# ThermistorFlex.net
KiCad netlist of a schematic drawn in EasyEDA Pro
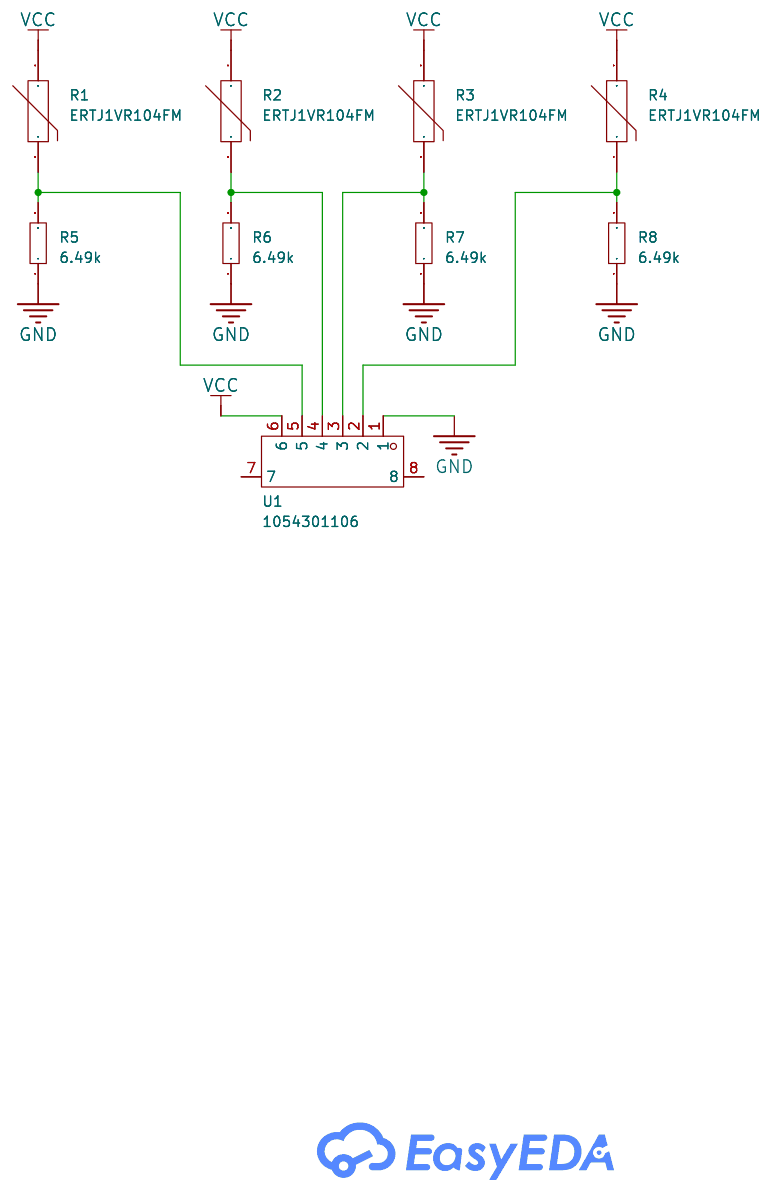
[diagram p0: schematic sheet]

(export (version "E")
  (design (tool "Eeschema 10.0.6"))
  (components
    (comp (ref "R1")
      (value "ERTJ1VR104FM")
      (footprint "easyedapro:R0603")
      (fields (field (name "Manufacturer") "PANASONIC(松下)"))
      (libsource (lib "easyedapro") (part "ERTJ1VR104FM"))
    )
    (comp (ref "R2")
      (value "ERTJ1VR104FM")
      (footprint "easyedapro:R0603")
      (fields (field (name "Manufacturer") "PANASONIC(松下)"))
      (libsource (lib "easyedapro") (part "ERTJ1VR104FM"))
    )
    (comp (ref "R3")
      (value "ERTJ1VR104FM")
      (footprint "easyedapro:R0603")
      (fields (field (name "Manufacturer") "PANASONIC(松下)"))
      (libsource (lib "easyedapro") (part "ERTJ1VR104FM"))
    )
    (comp (ref "R4")
      (value "ERTJ1VR104FM")
      (footprint "easyedapro:R0603")
      (fields (field (name "Manufacturer") "PANASONIC(松下)"))
      (libsource (lib "easyedapro") (part "ERTJ1VR104FM"))
    )
    (comp (ref "R5")
      (value "6.49k")
      (footprint "easyedapro:R0603")
      (libsource (lib "easyedapro") (part "Res"))
    )
    (comp (ref "R6")
      (value "6.49k")
      (footprint "easyedapro:R0603")
      (libsource (lib "easyedapro") (part "Res"))
    )
    (comp (ref "R7")
      (value "6.49k")
      (footprint "easyedapro:R0603")
      (libsource (lib "easyedapro") (part "Res"))
    )
    (comp (ref "R8")
      (value "6.49k")
      (footprint "easyedapro:R0603")
      (libsource (lib "easyedapro") (part "Res"))
    )
    (comp (ref "U1")
      (value "1054301106")
      (footprint "easyedapro:CONN-SMD_6P-P2.50_1054301106")
      (libsource (lib "easyedapro") (part "1054301106"))
    )
  )
  (nets
    (net (code "1") (name "GND") (class "Default")
      (node (ref "R5") (pin "1") (pinfunction "1_1") (pintype "input"))
      (node (ref "R6") (pin "1") (pinfunction "1_1") (pintype "input"))
      (node (ref "R7") (pin "1") (pinfunction "1_1") (pintype "input"))
      (node (ref "R8") (pin "1") (pinfunction "1_1") (pintype "input"))
      (node (ref "U1") (pin "1") (pinfunction "1_1") (pintype "unspecified"))
    )
    (net (code "2") (name "Net-(R1-Pad1)") (class "Default")
      (node (ref "R1") (pin "1") (pinfunction "1_1") (pintype "unspecified"))
      (node (ref "R5") (pin "2") (pinfunction "2_2") (pintype "input"))
      (node (ref "U1") (pin "5") (pinfunction "5_5") (pintype "unspecified"))
    )
    (net (code "3") (name "Net-(R2-Pad1)") (class "Default")
      (node (ref "R2") (pin "1") (pinfunction "1_1") (pintype "unspecified"))
      (node (ref "R6") (pin "2") (pinfunction "2_2") (pintype "input"))
      (node (ref "U1") (pin "4") (pinfunction "4_4") (pintype "unspecified"))
    )
    (net (code "4") (name "Net-(R3-Pad1)") (class "Default")
      (node (ref "R3") (pin "1") (pinfunction "1_1") (pintype "unspecified"))
      (node (ref "R7") (pin "2") (pinfunction "2_2") (pintype "input"))
      (node (ref "U1") (pin "3") (pinfunction "3_3") (pintype "unspecified"))
    )
    (net (code "5") (name "Net-(R4-Pad1)") (class "Default")
      (node (ref "R4") (pin "1") (pinfunction "1_1") (pintype "unspecified"))
      (node (ref "R8") (pin "2") (pinfunction "2_2") (pintype "input"))
      (node (ref "U1") (pin "2") (pinfunction "2_2") (pintype "unspecified"))
    )
    (net (code "6") (name "VCC") (class "Default")
      (node (ref "R1") (pin "2") (pinfunction "2_2") (pintype "unspecified"))
      (node (ref "R2") (pin "2") (pinfunction "2_2") (pintype "unspecified"))
      (node (ref "R3") (pin "2") (pinfunction "2_2") (pintype "unspecified"))
      (node (ref "R4") (pin "2") (pinfunction "2_2") (pintype "unspecified"))
      (node (ref "U1") (pin "6") (pinfunction "6_6") (pintype "unspecified"))
    )
    (net (code "7") (name "unconnected-(U1-Pad7)") (class "Default")
      (node (ref "U1") (pin "7") (pinfunction "7_7") (pintype "unspecified"))
    )
    (net (code "8") (name "unconnected-(U1-Pad8)") (class "Default")
      (node (ref "U1") (pin "8") (pinfunction "8_8") (pintype "unspecified"))
    )
  )
)
